# untitled.net
KiCad netlist of a schematic drawn in EAGLE
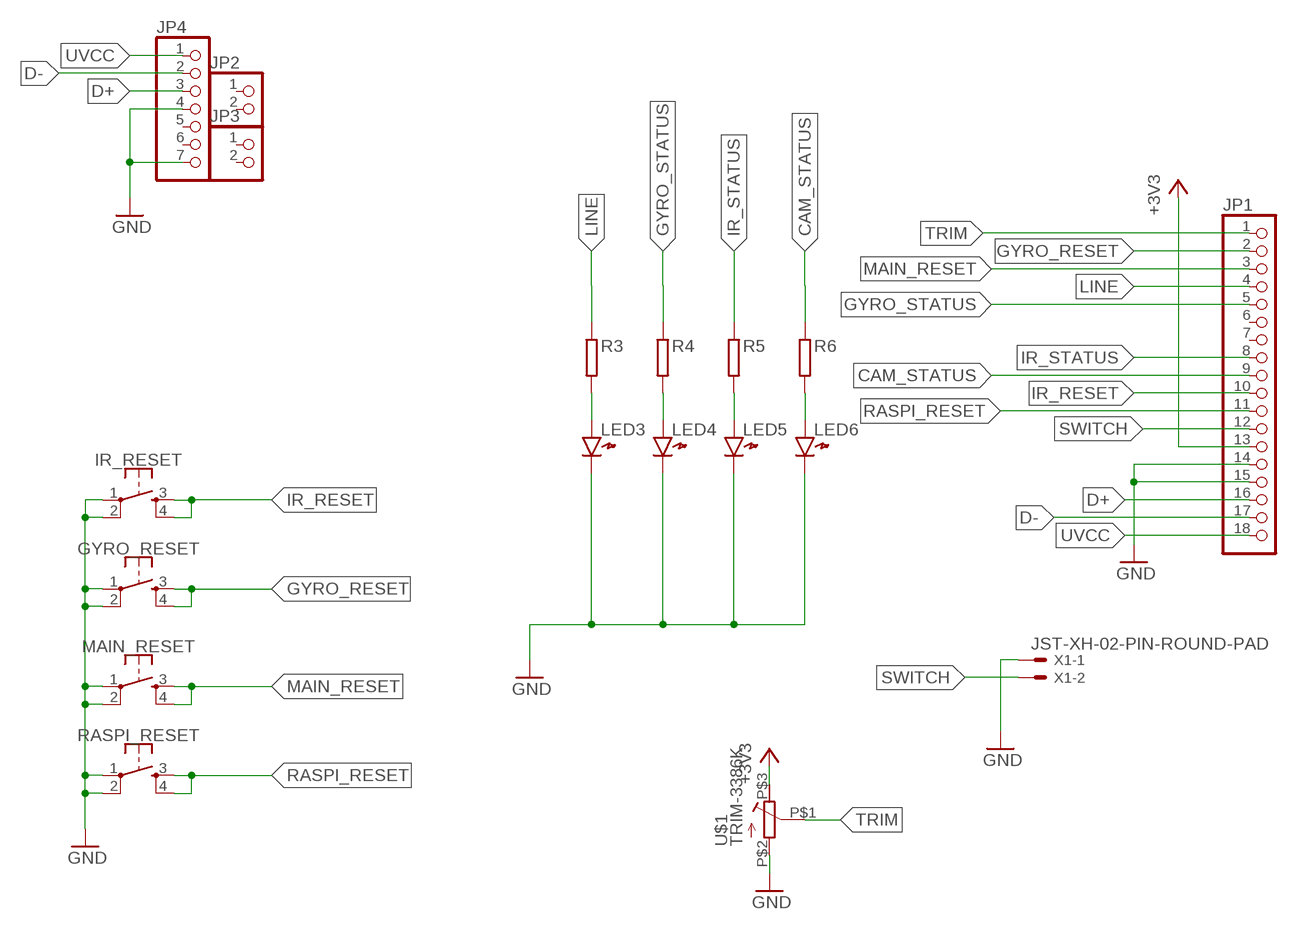
[diagram p0: schematic, sheet 1]

(export (version "E")
  (design (tool "Eeschema 10.0.6"))
  (components
    (comp (ref "GYRO_RESET")
      (value "MOMENTARY-SWITCH-SPST-2-SMD-5.2MM")
      (footprint "eagle-import:TACTILE_SWITCH_SMD_5.2MM")
      (libsource (lib "eagle-import") (part "MOMENTARY-SWITCH-SPST-2-SMD-5.2MM"))
    )
    (comp (ref "IR_RESET")
      (value "MOMENTARY-SWITCH-SPST-2-SMD-5.2MM")
      (footprint "eagle-import:TACTILE_SWITCH_SMD_5.2MM")
      (libsource (lib "eagle-import") (part "MOMENTARY-SWITCH-SPST-2-SMD-5.2MM"))
    )
    (comp (ref "JP1")
      (value "PINHD-1X18")
      (footprint "eagle-import:1X18")
      (libsource (lib "eagle-import") (part "PINHD-1X18"))
    )
    (comp (ref "JP2")
      (value "PINHD-1X2")
      (footprint "eagle-import:1X02")
      (libsource (lib "eagle-import") (part "PINHD-1X2"))
    )
    (comp (ref "JP3")
      (value "PINHD-1X2")
      (footprint "eagle-import:1X02")
      (libsource (lib "eagle-import") (part "PINHD-1X2"))
    )
    (comp (ref "JP4")
      (value "PINHD-1X7")
      (footprint "eagle-import:1X07")
      (libsource (lib "eagle-import") (part "PINHD-1X7"))
    )
    (comp (ref "LED3")
      (value "LED1608")
      (footprint "eagle-import:LED1608")
      (libsource (lib "eagle-import") (part "LED1608"))
    )
    (comp (ref "LED4")
      (value "LED1608")
      (footprint "eagle-import:LED1608")
      (libsource (lib "eagle-import") (part "LED1608"))
    )
    (comp (ref "LED5")
      (value "LED1608")
      (footprint "eagle-import:LED1608")
      (libsource (lib "eagle-import") (part "LED1608"))
    )
    (comp (ref "LED6")
      (value "LED1608")
      (footprint "eagle-import:LED1608")
      (libsource (lib "eagle-import") (part "LED1608"))
    )
    (comp (ref "MAIN_RESET")
      (value "MOMENTARY-SWITCH-SPST-2-SMD-5.2MM")
      (footprint "eagle-import:TACTILE_SWITCH_SMD_5.2MM")
      (libsource (lib "eagle-import") (part "MOMENTARY-SWITCH-SPST-2-SMD-5.2MM"))
    )
    (comp (ref "R3")
      (value "RESISTOR1608")
      (footprint "eagle-import:SMD1608")
      (libsource (lib "eagle-import") (part "RESISTOR1608"))
    )
    (comp (ref "R4")
      (value "RESISTOR1608")
      (footprint "eagle-import:SMD1608")
      (libsource (lib "eagle-import") (part "RESISTOR1608"))
    )
    (comp (ref "R5")
      (value "RESISTOR1608")
      (footprint "eagle-import:SMD1608")
      (libsource (lib "eagle-import") (part "RESISTOR1608"))
    )
    (comp (ref "R6")
      (value "RESISTOR1608")
      (footprint "eagle-import:SMD1608")
      (libsource (lib "eagle-import") (part "RESISTOR1608"))
    )
    (comp (ref "RASPI_RESET")
      (value "MOMENTARY-SWITCH-SPST-2-SMD-5.2MM")
      (footprint "eagle-import:TACTILE_SWITCH_SMD_5.2MM")
      (libsource (lib "eagle-import") (part "MOMENTARY-SWITCH-SPST-2-SMD-5.2MM"))
    )
    (comp (ref "U$1")
      (value "TRIM-3386K")
      (footprint "eagle-import:TRIM-3386K")
      (libsource (lib "eagle-import") (part "TRIM-3386K"))
    )
    (comp (ref "X1")
      (value "JST-XH-02-PIN-ROUND-PAD")
      (footprint "eagle-import:JST-XH-02-PACKAGE-ROUND-PAD")
      (libsource (lib "eagle-import") (part "JST-XH-02-PIN-ROUND-PAD"))
    )
  )
  (nets
    (net (code "1") (name "+3V3") (class "Default")
      (node (ref "JP1") (pin "13") (pinfunction "13_13") (pintype "passive"))
      (node (ref "U$1") (pin "P$3") (pinfunction "1_P$3") (pintype "passive"))
    )
    (net (code "2") (name "CAM_STATUS") (class "Default")
      (node (ref "JP1") (pin "9") (pinfunction "9_9") (pintype "passive"))
      (node (ref "R6") (pin "1") (pinfunction "1_1") (pintype "passive"))
    )
    (net (code "3") (name "D+") (class "Default")
      (node (ref "JP1") (pin "16") (pinfunction "16_16") (pintype "passive"))
      (node (ref "JP4") (pin "3") (pinfunction "3_3") (pintype "passive"))
    )
    (net (code "4") (name "D-") (class "Default")
      (node (ref "JP1") (pin "17") (pinfunction "17_17") (pintype "passive"))
      (node (ref "JP4") (pin "2") (pinfunction "2_2") (pintype "passive"))
    )
    (net (code "5") (name "GND") (class "Default")
      (node (ref "GYRO_RESET") (pin "1") (pinfunction "1_1") (pintype "passive"))
      (node (ref "GYRO_RESET") (pin "2") (pinfunction "2_2") (pintype "passive"))
      (node (ref "IR_RESET") (pin "1") (pinfunction "1_1") (pintype "passive"))
      (node (ref "IR_RESET") (pin "2") (pinfunction "2_2") (pintype "passive"))
      (node (ref "JP1") (pin "14") (pinfunction "14_14") (pintype "passive"))
      (node (ref "JP1") (pin "15") (pinfunction "15_15") (pintype "passive"))
      (node (ref "JP4") (pin "4") (pinfunction "4_4") (pintype "passive"))
      (node (ref "JP4") (pin "7") (pinfunction "7_7") (pintype "passive"))
      (node (ref "LED3") (pin "K") (pinfunction "K_K") (pintype "passive"))
      (node (ref "LED4") (pin "K") (pinfunction "K_K") (pintype "passive"))
      (node (ref "LED5") (pin "K") (pinfunction "K_K") (pintype "passive"))
      (node (ref "LED6") (pin "K") (pinfunction "K_K") (pintype "passive"))
      (node (ref "MAIN_RESET") (pin "1") (pinfunction "1_1") (pintype "passive"))
      (node (ref "MAIN_RESET") (pin "2") (pinfunction "2_2") (pintype "passive"))
      (node (ref "RASPI_RESET") (pin "1") (pinfunction "1_1") (pintype "passive"))
      (node (ref "RASPI_RESET") (pin "2") (pinfunction "2_2") (pintype "passive"))
      (node (ref "U$1") (pin "P$2") (pinfunction "2_P$2") (pintype "passive"))
      (node (ref "X1") (pin "1") (pinfunction "S_1") (pintype "passive"))
    )
    (net (code "6") (name "GYRO_RESET") (class "Default")
      (node (ref "GYRO_RESET") (pin "3") (pinfunction "3_3") (pintype "passive"))
      (node (ref "GYRO_RESET") (pin "4") (pinfunction "4_4") (pintype "passive"))
      (node (ref "JP1") (pin "2") (pinfunction "2_2") (pintype "passive"))
    )
    (net (code "7") (name "GYRO_STATUS") (class "Default")
      (node (ref "JP1") (pin "5") (pinfunction "5_5") (pintype "passive"))
      (node (ref "R4") (pin "1") (pinfunction "1_1") (pintype "passive"))
    )
    (net (code "8") (name "IR_RESET") (class "Default")
      (node (ref "IR_RESET") (pin "3") (pinfunction "3_3") (pintype "passive"))
      (node (ref "IR_RESET") (pin "4") (pinfunction "4_4") (pintype "passive"))
      (node (ref "JP1") (pin "10") (pinfunction "10_10") (pintype "passive"))
    )
    (net (code "9") (name "IR_STATUS") (class "Default")
      (node (ref "JP1") (pin "8") (pinfunction "8_8") (pintype "passive"))
      (node (ref "R5") (pin "1") (pinfunction "1_1") (pintype "passive"))
    )
    (net (code "10") (name "LINE") (class "Default")
      (node (ref "JP1") (pin "4") (pinfunction "4_4") (pintype "passive"))
      (node (ref "R3") (pin "1") (pinfunction "1_1") (pintype "passive"))
    )
    (net (code "11") (name "MAIN_RESET") (class "Default")
      (node (ref "JP1") (pin "3") (pinfunction "3_3") (pintype "passive"))
      (node (ref "MAIN_RESET") (pin "3") (pinfunction "3_3") (pintype "passive"))
      (node (ref "MAIN_RESET") (pin "4") (pinfunction "4_4") (pintype "passive"))
    )
    (net (code "12") (name "Net-(LED3-PadA)") (class "Default")
      (node (ref "LED3") (pin "A") (pinfunction "A_A") (pintype "passive"))
      (node (ref "R3") (pin "2") (pinfunction "2_2") (pintype "passive"))
    )
    (net (code "13") (name "Net-(LED4-PadA)") (class "Default")
      (node (ref "LED4") (pin "A") (pinfunction "A_A") (pintype "passive"))
      (node (ref "R4") (pin "2") (pinfunction "2_2") (pintype "passive"))
    )
    (net (code "14") (name "Net-(LED5-PadA)") (class "Default")
      (node (ref "LED5") (pin "A") (pinfunction "A_A") (pintype "passive"))
      (node (ref "R5") (pin "2") (pinfunction "2_2") (pintype "passive"))
    )
    (net (code "15") (name "Net-(LED6-PadA)") (class "Default")
      (node (ref "LED6") (pin "A") (pinfunction "A_A") (pintype "passive"))
      (node (ref "R6") (pin "2") (pinfunction "2_2") (pintype "passive"))
    )
    (net (code "16") (name "RASPI_RESET") (class "Default")
      (node (ref "JP1") (pin "11") (pinfunction "11_11") (pintype "passive"))
      (node (ref "RASPI_RESET") (pin "3") (pinfunction "3_3") (pintype "passive"))
      (node (ref "RASPI_RESET") (pin "4") (pinfunction "4_4") (pintype "passive"))
    )
    (net (code "17") (name "SWITCH") (class "Default")
      (node (ref "JP1") (pin "12") (pinfunction "12_12") (pintype "passive"))
      (node (ref "X1") (pin "2") (pinfunction "S_2") (pintype "passive"))
    )
    (net (code "18") (name "TRIM") (class "Default")
      (node (ref "JP1") (pin "1") (pinfunction "1_1") (pintype "passive"))
      (node (ref "U$1") (pin "P$1") (pinfunction "3_P$1") (pintype "passive"))
    )
    (net (code "19") (name "UVCC") (class "Default")
      (node (ref "JP1") (pin "18") (pinfunction "18_18") (pintype "passive"))
      (node (ref "JP4") (pin "1") (pinfunction "1_1") (pintype "passive"))
    )
    (net (code "20") (name "unconnected-(JP1-Pad6)") (class "Default")
      (node (ref "JP1") (pin "6") (pinfunction "6_6") (pintype "passive"))
    )
    (net (code "21") (name "unconnected-(JP1-Pad7)") (class "Default")
      (node (ref "JP1") (pin "7") (pinfunction "7_7") (pintype "passive"))
    )
    (net (code "22") (name "unconnected-(JP2-Pad1)") (class "Default")
      (node (ref "JP2") (pin "1") (pinfunction "1_1") (pintype "passive"))
    )
    (net (code "23") (name "unconnected-(JP2-Pad2)") (class "Default")
      (node (ref "JP2") (pin "2") (pinfunction "2_2") (pintype "passive"))
    )
    (net (code "24") (name "unconnected-(JP3-Pad1)") (class "Default")
      (node (ref "JP3") (pin "1") (pinfunction "1_1") (pintype "passive"))
    )
    (net (code "25") (name "unconnected-(JP3-Pad2)") (class "Default")
      (node (ref "JP3") (pin "2") (pinfunction "2_2") (pintype "passive"))
    )
    (net (code "26") (name "unconnected-(JP4-Pad5)") (class "Default")
      (node (ref "JP4") (pin "5") (pinfunction "5_5") (pintype "passive"))
    )
    (net (code "27") (name "unconnected-(JP4-Pad6)") (class "Default")
      (node (ref "JP4") (pin "6") (pinfunction "6_6") (pintype "passive"))
    )
  )
)
